# 3_P3.net
KiCad netlist of a schematic drawn in Altium Designer
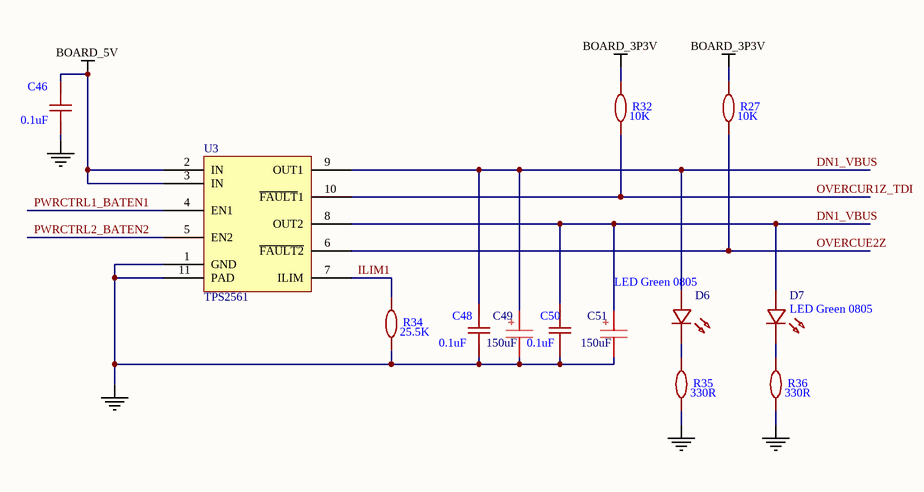
[diagram p0: 3_P3.schdoc]

(export (version "E")
  (design (tool "Eeschema 10.0.6"))
  (components
    (comp (ref "C46")
      (value "0.1uF")
      (footprint "C0603")
      (libsource (lib "altium-import") (part "root_1_CAP_0603_"))
    )
    (comp (ref "C48")
      (value "0.1uF")
      (footprint "C0603")
      (libsource (lib "altium-import") (part "root_1_CAP_0603_"))
    )
    (comp (ref "C49") (value "150uF") (footprint "C0603") (libsource (lib "Schlib1") (part "CAP")))
    (comp (ref "C50")
      (value "0.1uF")
      (footprint "C0603")
      (libsource (lib "altium-import") (part "root_1_CAP_0603_"))
    )
    (comp (ref "C51") (value "150uF") (footprint "C0603") (libsource (lib "Schlib1") (part "CAP")))
    (comp (ref "D6")
      (value "LED Green 0805")
      (footprint "LED_0805")
      (libsource (lib "altium-import") (part "root_3_LED_0805-G_"))
    )
    (comp (ref "D7")
      (value "LED Green 0805")
      (footprint "LED_0805")
      (libsource (lib "altium-import") (part "root_3_LED_0805-G_"))
    )
    (comp (ref "R27")
      (value "10K")
      (footprint "R0603")
      (libsource (lib "altium-import") (part "root_1_Res_0603_"))
    )
    (comp (ref "R32")
      (value "10K")
      (footprint "R0603")
      (libsource (lib "altium-import") (part "root_1_Res_0603_"))
    )
    (comp (ref "R34")
      (value "25.5K")
      (footprint "R0603")
      (libsource (lib "altium-import") (part "root_1_Res_0603_"))
    )
    (comp (ref "R35")
      (value "330R")
      (footprint "R0603")
      (libsource (lib "altium-import") (part "root_1_Res_0603_"))
    )
    (comp (ref "R36")
      (value "330R")
      (footprint "R0603")
      (libsource (lib "altium-import") (part "root_1_Res_0603_"))
    )
    (comp (ref "U3")
      (value "TPS2561")
      (footprint "TI_TPS2561_VSON-10")
      (libsource (lib "Schlib1") (part "TPS2561"))
    )
  )
  (nets
    (net (code "1") (name "/DN1_VBUS") (class "Default")
      (node (ref "C48") (pin "2") (pinfunction "2_2") (pintype "passive"))
      (node (ref "C49") (pin "1") (pintype "passive"))
      (node (ref "C50") (pin "2") (pinfunction "2_2") (pintype "passive"))
      (node (ref "C51") (pin "1") (pintype "passive"))
      (node (ref "D6") (pin "2") (pinfunction "A_2") (pintype "passive"))
      (node (ref "D7") (pin "2") (pinfunction "A_2") (pintype "passive"))
      (node (ref "U3") (pin "8") (pinfunction "OUT2_8") (pintype "passive"))
      (node (ref "U3") (pin "9") (pinfunction "OUT1_9") (pintype "passive"))
    )
    (net (code "2") (name "/ILIM1") (class "Default")
      (node (ref "R34") (pin "2") (pinfunction "2_2") (pintype "passive"))
      (node (ref "U3") (pin "7") (pinfunction "ILIM_7") (pintype "passive"))
    )
    (net (code "3") (name "/OVERCUE2Z") (class "Default")
      (node (ref "R27") (pin "1") (pinfunction "1_1") (pintype "passive"))
      (node (ref "U3") (pin "6") (pinfunction "~{FAULT2}_6") (pintype "passive"))
    )
    (net (code "4") (name "/OVERCUR1Z_TDI") (class "Default")
      (node (ref "R32") (pin "1") (pinfunction "1_1") (pintype "passive"))
      (node (ref "U3") (pin "10") (pinfunction "~{FAULT}1_10") (pintype "passive"))
    )
    (net (code "5") (name "/PWRCTRL1_BATEN1") (class "Default")
      (node (ref "U3") (pin "4") (pinfunction "EN1_4") (pintype "passive"))
    )
    (net (code "6") (name "/PWRCTRL2_BATEN2") (class "Default")
      (node (ref "U3") (pin "5") (pinfunction "EN2_5") (pintype "passive"))
    )
    (net (code "7") (name "BOARD_3P3V") (class "Default")
      (node (ref "R27") (pin "2") (pinfunction "2_2") (pintype "passive"))
      (node (ref "R32") (pin "2") (pinfunction "2_2") (pintype "passive"))
    )
    (net (code "8") (name "BOARD_5V") (class "Default")
      (node (ref "C46") (pin "2") (pinfunction "2_2") (pintype "passive"))
      (node (ref "U3") (pin "2") (pinfunction "IN_2") (pintype "passive"))
      (node (ref "U3") (pin "3") (pinfunction "IN_3") (pintype "passive"))
    )
    (net (code "9") (name "GND") (class "Default")
      (node (ref "C46") (pin "1") (pinfunction "1_1") (pintype "passive"))
      (node (ref "C48") (pin "1") (pinfunction "1_1") (pintype "passive"))
      (node (ref "C49") (pin "2") (pintype "passive"))
      (node (ref "C50") (pin "1") (pinfunction "1_1") (pintype "passive"))
      (node (ref "C51") (pin "2") (pintype "passive"))
      (node (ref "R34") (pin "1") (pinfunction "1_1") (pintype "passive"))
      (node (ref "R35") (pin "1") (pinfunction "1_1") (pintype "passive"))
      (node (ref "R36") (pin "1") (pinfunction "1_1") (pintype "passive"))
      (node (ref "U3") (pin "1") (pinfunction "GND_1") (pintype "passive"))
      (node (ref "U3") (pin "11") (pinfunction "PAD_11") (pintype "passive"))
    )
    (net (code "10") (name "Net-(D6-C)") (class "Default")
      (node (ref "D6") (pin "1") (pinfunction "C_1") (pintype "passive"))
      (node (ref "R35") (pin "2") (pinfunction "2_2") (pintype "passive"))
    )
    (net (code "11") (name "Net-(D7-C)") (class "Default")
      (node (ref "D7") (pin "1") (pinfunction "C_1") (pintype "passive"))
      (node (ref "R36") (pin "2") (pinfunction "2_2") (pintype "passive"))
    )
  )
)
